# PROC010B_Decoupling_Caps_Reference.net
KiCad netlist of a schematic drawn in Altium Designer
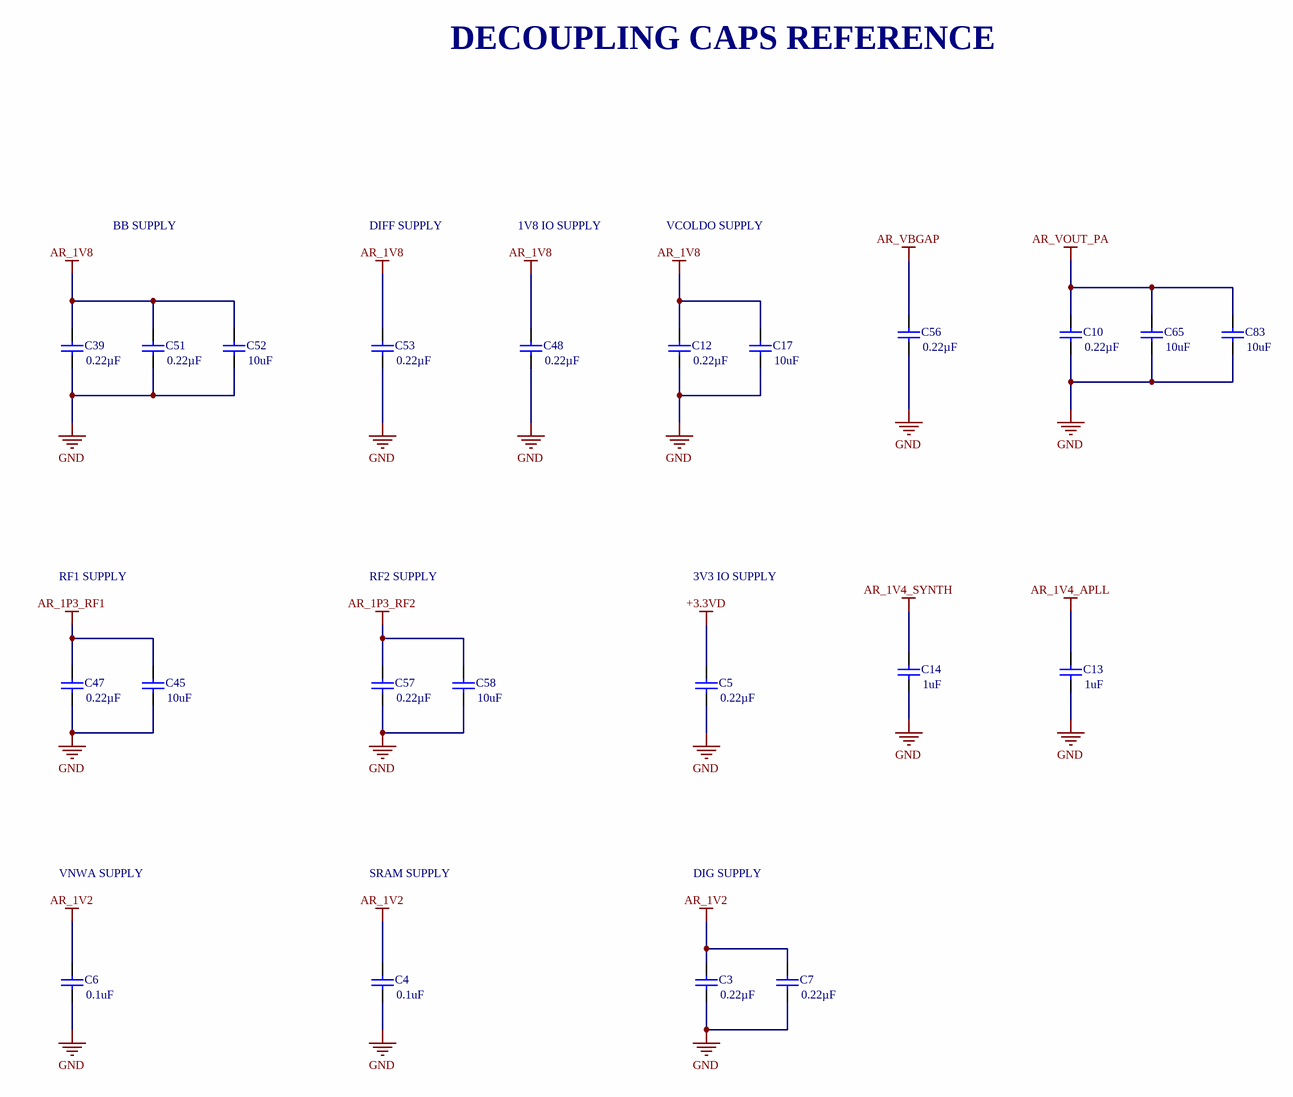
[diagram p0: PROC010B_Decoupling_Caps_Reference.SchDoc]

(export (version "E")
  (design (tool "Eeschema 10.0.6"))
  (components
    (comp (ref "C3")
      (value "GCM155R71C224KE02D")
      (footprint "0402L")
      (description "CAP, CERM, 0.22 µF, 16 V,+/- 10%, X7R, AEC-Q200 Grade 1, 0402")
      (fields (field (name "MANUFACTURER") "MuRata") (field (name "VALUEDISPLAYED") "0.22µF"))
      (libsource (lib "Altium Vault - TI") (part "CMP-0078265-1"))
    )
    (comp (ref "C4")
      (value "GCM155R71C104KA55D")
      (footprint "0402L")
      (description "CAP, CERM, 0.1 uF, 16 V, +/- 10%, X7R, 0402")
      (fields
        (field (name "MANUFACTURER") "MuRata")
        (field (name "VALUEDISPLAYED") "0.1uF")
        (field (name "PUBLISHER") "Texas Instruments")
      )
      (libsource (lib "Altium Vault - TI") (part "CMP-0006351-2"))
    )
    (comp (ref "C5")
      (value "GCM155R71C224KE02D")
      (footprint "0402L")
      (description "CAP, CERM, 0.22 µF, 16 V,+/- 10%, X7R, AEC-Q200 Grade 1, 0402")
      (fields (field (name "MANUFACTURER") "MuRata") (field (name "VALUEDISPLAYED") "0.22µF"))
      (libsource (lib "Altium Vault - TI") (part "CMP-0078265-1"))
    )
    (comp (ref "C6")
      (value "GCM155R71C104KA55D")
      (footprint "0402")
      (description "CAP, CERM, 0.1 uF, 16 V, +/- 10%, X7R, 0402")
      (fields
        (field (name "MANUFACTURER") "MuRata")
        (field (name "VALUEDISPLAYED") "0.1uF")
        (field (name "PUBLISHER") "Texas Instruments")
      )
      (libsource (lib "Altium Vault - TI") (part "Capacitor"))
    )
    (comp (ref "C7")
      (value "GCM155R71C224KE02D")
      (footprint "0402L")
      (description "CAP, CERM, 0.22 µF, 16 V,+/- 10%, X7R, AEC-Q200 Grade 1, 0402")
      (fields (field (name "MANUFACTURER") "MuRata") (field (name "VALUEDISPLAYED") "0.22µF"))
      (libsource (lib "Altium Vault - TI") (part "CMP-0078265-1"))
    )
    (comp (ref "C10")
      (value "GCM155R71C224KE02D")
      (footprint "0402")
      (description "CAP, CERM, 0.22 µF, 16 V,+/- 10%, X7R, AEC-Q200 Grade 1, 0402")
      (fields (field (name "MANUFACTURER") "MuRata") (field (name "VALUEDISPLAYED") "0.22µF"))
      (libsource (lib "Altium Vault - TI") (part "Capacitor"))
    )
    (comp (ref "C12")
      (value "GCM155R71C224KE02D")
      (footprint "0402")
      (description "CAP, CERM, 0.22 µF, 16 V,+/- 10%, X7R, AEC-Q200 Grade 1, 0402")
      (fields (field (name "MANUFACTURER") "MuRata") (field (name "VALUEDISPLAYED") "0.22µF"))
      (libsource (lib "Altium Vault - TI") (part "Capacitor"))
    )
    (comp (ref "C13")
      (value "GCM188R71C105KA64D")
      (footprint "0603")
      (description "CAP, CERM, 1 uF, 16 V, +/- 10%, X7R, AEC-Q200 Grade 1, 0603")
      (fields
        (field (name "MANUFACTURER") "MuRata")
        (field (name "VALUEDISPLAYED") "1uF")
        (field (name "PUBLISHER") "Texas Instruments")
      )
      (libsource (lib "Altium Vault - TI") (part "Capacitor"))
    )
    (comp (ref "C14")
      (value "GCM188R71C105KA64D")
      (footprint "0603")
      (description "CAP, CERM, 1 uF, 16 V, +/- 10%, X7R, AEC-Q200 Grade 1, 0603")
      (fields
        (field (name "MANUFACTURER") "MuRata")
        (field (name "VALUEDISPLAYED") "1uF")
        (field (name "PUBLISHER") "Texas Instruments")
      )
      (libsource (lib "Altium Vault - TI") (part "Capacitor"))
    )
    (comp (ref "C17")
      (value "GCM21BR71A106KE22L")
      (footprint "0805_HV")
      (description "CAP, CERM, 10 uF, 10 V, +/- 10%, X7R, 0805")
      (fields
        (field (name "MANUFACTURER") "MuRata")
        (field (name "VALUEDISPLAYED") "10uF")
        (field (name "PUBLISHER") "Texas Instruments")
      )
      (libsource (lib "Altium Vault - TI") (part "Capacitor"))
    )
    (comp (ref "C39")
      (value "GCM155R71C224KE02D")
      (footprint "0402L")
      (description "CAP, CERM, 0.22 µF, 16 V,+/- 10%, X7R, AEC-Q200 Grade 1, 0402")
      (fields (field (name "MANUFACTURER") "MuRata") (field (name "VALUEDISPLAYED") "0.22µF"))
      (libsource (lib "Altium Vault - TI") (part "CMP-0078265-1"))
    )
    (comp (ref "C45")
      (value "GCM21BR71A106KE22L")
      (footprint "0805_HV1")
      (description "CAP, CERM, 10 uF, 10 V, +/- 10%, X7R, 0805")
      (fields
        (field (name "MANUFACTURER") "MuRata")
        (field (name "VALUEDISPLAYED") "10uF")
        (field (name "PUBLISHER") "Texas Instruments")
      )
      (libsource (lib "Altium Vault - TI") (part "CMP-0008017-2"))
    )
    (comp (ref "C47")
      (value "GCM155R71C224KE02D")
      (footprint "0402L")
      (description "CAP, CERM, 0.22 µF, 16 V,+/- 10%, X7R, AEC-Q200 Grade 1, 0402")
      (fields (field (name "MANUFACTURER") "MuRata") (field (name "VALUEDISPLAYED") "0.22µF"))
      (libsource (lib "Altium Vault - TI") (part "CMP-0078265-1"))
    )
    (comp (ref "C48")
      (value "GCM155R71C224KE02D")
      (footprint "0402")
      (description "CAP, CERM, 0.22 µF, 16 V,+/- 10%, X7R, AEC-Q200 Grade 1, 0402")
      (fields (field (name "MANUFACTURER") "MuRata") (field (name "VALUEDISPLAYED") "0.22µF"))
      (libsource (lib "Altium Vault - TI") (part "Capacitor"))
    )
    (comp (ref "C51")
      (value "GCM155R71C224KE02D")
      (footprint "0402")
      (description "CAP, CERM, 0.22 µF, 16 V,+/- 10%, X7R, AEC-Q200 Grade 1, 0402")
      (fields (field (name "MANUFACTURER") "MuRata") (field (name "VALUEDISPLAYED") "0.22µF"))
      (libsource (lib "Altium Vault - TI") (part "Capacitor"))
    )
    (comp (ref "C52")
      (value "GCM21BR71A106KE22L")
      (footprint "0805_HV")
      (description "CAP, CERM, 10 uF, 10 V, +/- 10%, X7R, 0805")
      (fields
        (field (name "MANUFACTURER") "MuRata")
        (field (name "VALUEDISPLAYED") "10uF")
        (field (name "PUBLISHER") "Texas Instruments")
      )
      (libsource (lib "Altium Vault - TI") (part "Capacitor"))
    )
    (comp (ref "C53")
      (value "GCM155R71C224KE02D")
      (footprint "0402")
      (description "CAP, CERM, 0.22 µF, 16 V,+/- 10%, X7R, AEC-Q200 Grade 1, 0402")
      (fields (field (name "MANUFACTURER") "MuRata") (field (name "VALUEDISPLAYED") "0.22µF"))
      (libsource (lib "Altium Vault - TI") (part "Capacitor"))
    )
    (comp (ref "C56")
      (value "GCM155R71C224KE02D")
      (footprint "0402")
      (description "CAP, CERM, 0.22 µF, 16 V,+/- 10%, X7R, AEC-Q200 Grade 1, 0402")
      (fields (field (name "MANUFACTURER") "MuRata") (field (name "VALUEDISPLAYED") "0.22µF"))
      (libsource (lib "Altium Vault - TI") (part "Capacitor"))
    )
    (comp (ref "C57")
      (value "GCM155R71C224KE02D")
      (footprint "0402")
      (description "CAP, CERM, 0.22 µF, 16 V,+/- 10%, X7R, AEC-Q200 Grade 1, 0402")
      (fields (field (name "MANUFACTURER") "MuRata") (field (name "VALUEDISPLAYED") "0.22µF"))
      (libsource (lib "Altium Vault - TI") (part "Capacitor"))
    )
    (comp (ref "C58")
      (value "GCM21BR71A106KE22L")
      (footprint "0805")
      (description "CAP, CERM, 10 uF, 10 V, +/- 10%, X7R, 0805")
      (fields
        (field (name "MANUFACTURER") "MuRata")
        (field (name "VALUEDISPLAYED") "10uF")
        (field (name "PUBLISHER") "Texas Instruments")
      )
      (libsource (lib "Altium Vault - TI") (part "CMP-0008017-2"))
    )
    (comp (ref "C65")
      (value "GCM21BR71A106KE22L")
      (footprint "0805_HV")
      (description "CAP, CERM, 10 uF, 10 V, +/- 10%, X7R, 0805")
      (fields
        (field (name "MANUFACTURER") "MuRata")
        (field (name "VALUEDISPLAYED") "10uF")
        (field (name "PUBLISHER") "Texas Instruments")
      )
      (libsource (lib "Altium Vault - TI") (part "Capacitor"))
    )
    (comp (ref "C83")
      (value "GCM21BR71A106KE22L")
      (footprint "0805_HV")
      (description "CAP, CERM, 10 uF, 10 V, +/- 10%, X7R, 0805")
      (fields
        (field (name "MANUFACTURER") "MuRata")
        (field (name "VALUEDISPLAYED") "10uF")
        (field (name "PUBLISHER") "Texas Instruments")
      )
      (libsource (lib "Altium Vault - TI") (part "Capacitor"))
    )
  )
  (nets
    (net (code "1") (name "+3.3VD") (class "Default")
      (node (ref "C5") (pin "1") (pinfunction "1_1") (pintype "passive"))
    )
    (net (code "2") (name "AR_1P3_RF1") (class "Default")
      (node (ref "C45") (pin "1") (pinfunction "1_1") (pintype "passive"))
      (node (ref "C47") (pin "1") (pinfunction "1_1") (pintype "passive"))
    )
    (net (code "3") (name "AR_1P3_RF2") (class "Default")
      (node (ref "C57") (pin "1") (pinfunction "1_1") (pintype "passive"))
      (node (ref "C58") (pin "1") (pinfunction "1_1") (pintype "passive"))
    )
    (net (code "4") (name "AR_1V2") (class "Default")
      (node (ref "C3") (pin "1") (pinfunction "1_1") (pintype "passive"))
      (node (ref "C4") (pin "1") (pinfunction "1_1") (pintype "passive"))
      (node (ref "C6") (pin "1") (pinfunction "1_1") (pintype "passive"))
      (node (ref "C7") (pin "1") (pinfunction "1_1") (pintype "passive"))
    )
    (net (code "5") (name "AR_1V4_APLL") (class "Default")
      (node (ref "C13") (pin "1") (pinfunction "1_1") (pintype "passive"))
    )
    (net (code "6") (name "AR_1V4_SYNTH") (class "Default")
      (node (ref "C14") (pin "1") (pinfunction "1_1") (pintype "passive"))
    )
    (net (code "7") (name "AR_1V8") (class "Default")
      (node (ref "C12") (pin "1") (pinfunction "1_1") (pintype "passive"))
      (node (ref "C17") (pin "1") (pinfunction "1_1") (pintype "passive"))
      (node (ref "C39") (pin "1") (pinfunction "1_1") (pintype "passive"))
      (node (ref "C48") (pin "1") (pinfunction "1_1") (pintype "passive"))
      (node (ref "C51") (pin "1") (pinfunction "1_1") (pintype "passive"))
      (node (ref "C52") (pin "1") (pinfunction "1_1") (pintype "passive"))
      (node (ref "C53") (pin "1") (pinfunction "1_1") (pintype "passive"))
    )
    (net (code "8") (name "AR_VBGAP") (class "Default")
      (node (ref "C56") (pin "1") (pinfunction "1_1") (pintype "passive"))
    )
    (net (code "9") (name "AR_VOUT_PA") (class "Default")
      (node (ref "C10") (pin "1") (pinfunction "1_1") (pintype "passive"))
      (node (ref "C65") (pin "1") (pinfunction "1_1") (pintype "passive"))
      (node (ref "C83") (pin "1") (pinfunction "1_1") (pintype "passive"))
    )
    (net (code "10") (name "GND") (class "Default")
      (node (ref "C10") (pin "2") (pinfunction "2_2") (pintype "passive"))
      (node (ref "C12") (pin "2") (pinfunction "2_2") (pintype "passive"))
      (node (ref "C13") (pin "2") (pinfunction "2_2") (pintype "passive"))
      (node (ref "C14") (pin "2") (pinfunction "2_2") (pintype "passive"))
      (node (ref "C17") (pin "2") (pinfunction "2_2") (pintype "passive"))
      (node (ref "C3") (pin "2") (pinfunction "2_2") (pintype "passive"))
      (node (ref "C39") (pin "2") (pinfunction "2_2") (pintype "passive"))
      (node (ref "C4") (pin "2") (pinfunction "2_2") (pintype "passive"))
      (node (ref "C45") (pin "2") (pinfunction "2_2") (pintype "passive"))
      (node (ref "C47") (pin "2") (pinfunction "2_2") (pintype "passive"))
      (node (ref "C48") (pin "2") (pinfunction "2_2") (pintype "passive"))
      (node (ref "C5") (pin "2") (pinfunction "2_2") (pintype "passive"))
      (node (ref "C51") (pin "2") (pinfunction "2_2") (pintype "passive"))
      (node (ref "C52") (pin "2") (pinfunction "2_2") (pintype "passive"))
      (node (ref "C53") (pin "2") (pinfunction "2_2") (pintype "passive"))
      (node (ref "C56") (pin "2") (pinfunction "2_2") (pintype "passive"))
      (node (ref "C57") (pin "2") (pinfunction "2_2") (pintype "passive"))
      (node (ref "C58") (pin "2") (pinfunction "2_2") (pintype "passive"))
      (node (ref "C6") (pin "2") (pinfunction "2_2") (pintype "passive"))
      (node (ref "C65") (pin "2") (pinfunction "2_2") (pintype "passive"))
      (node (ref "C7") (pin "2") (pinfunction "2_2") (pintype "passive"))
      (node (ref "C83") (pin "2") (pinfunction "2_2") (pintype "passive"))
    )
  )
)
